# page1.net
KiCad netlist of a schematic drawn in EAGLE
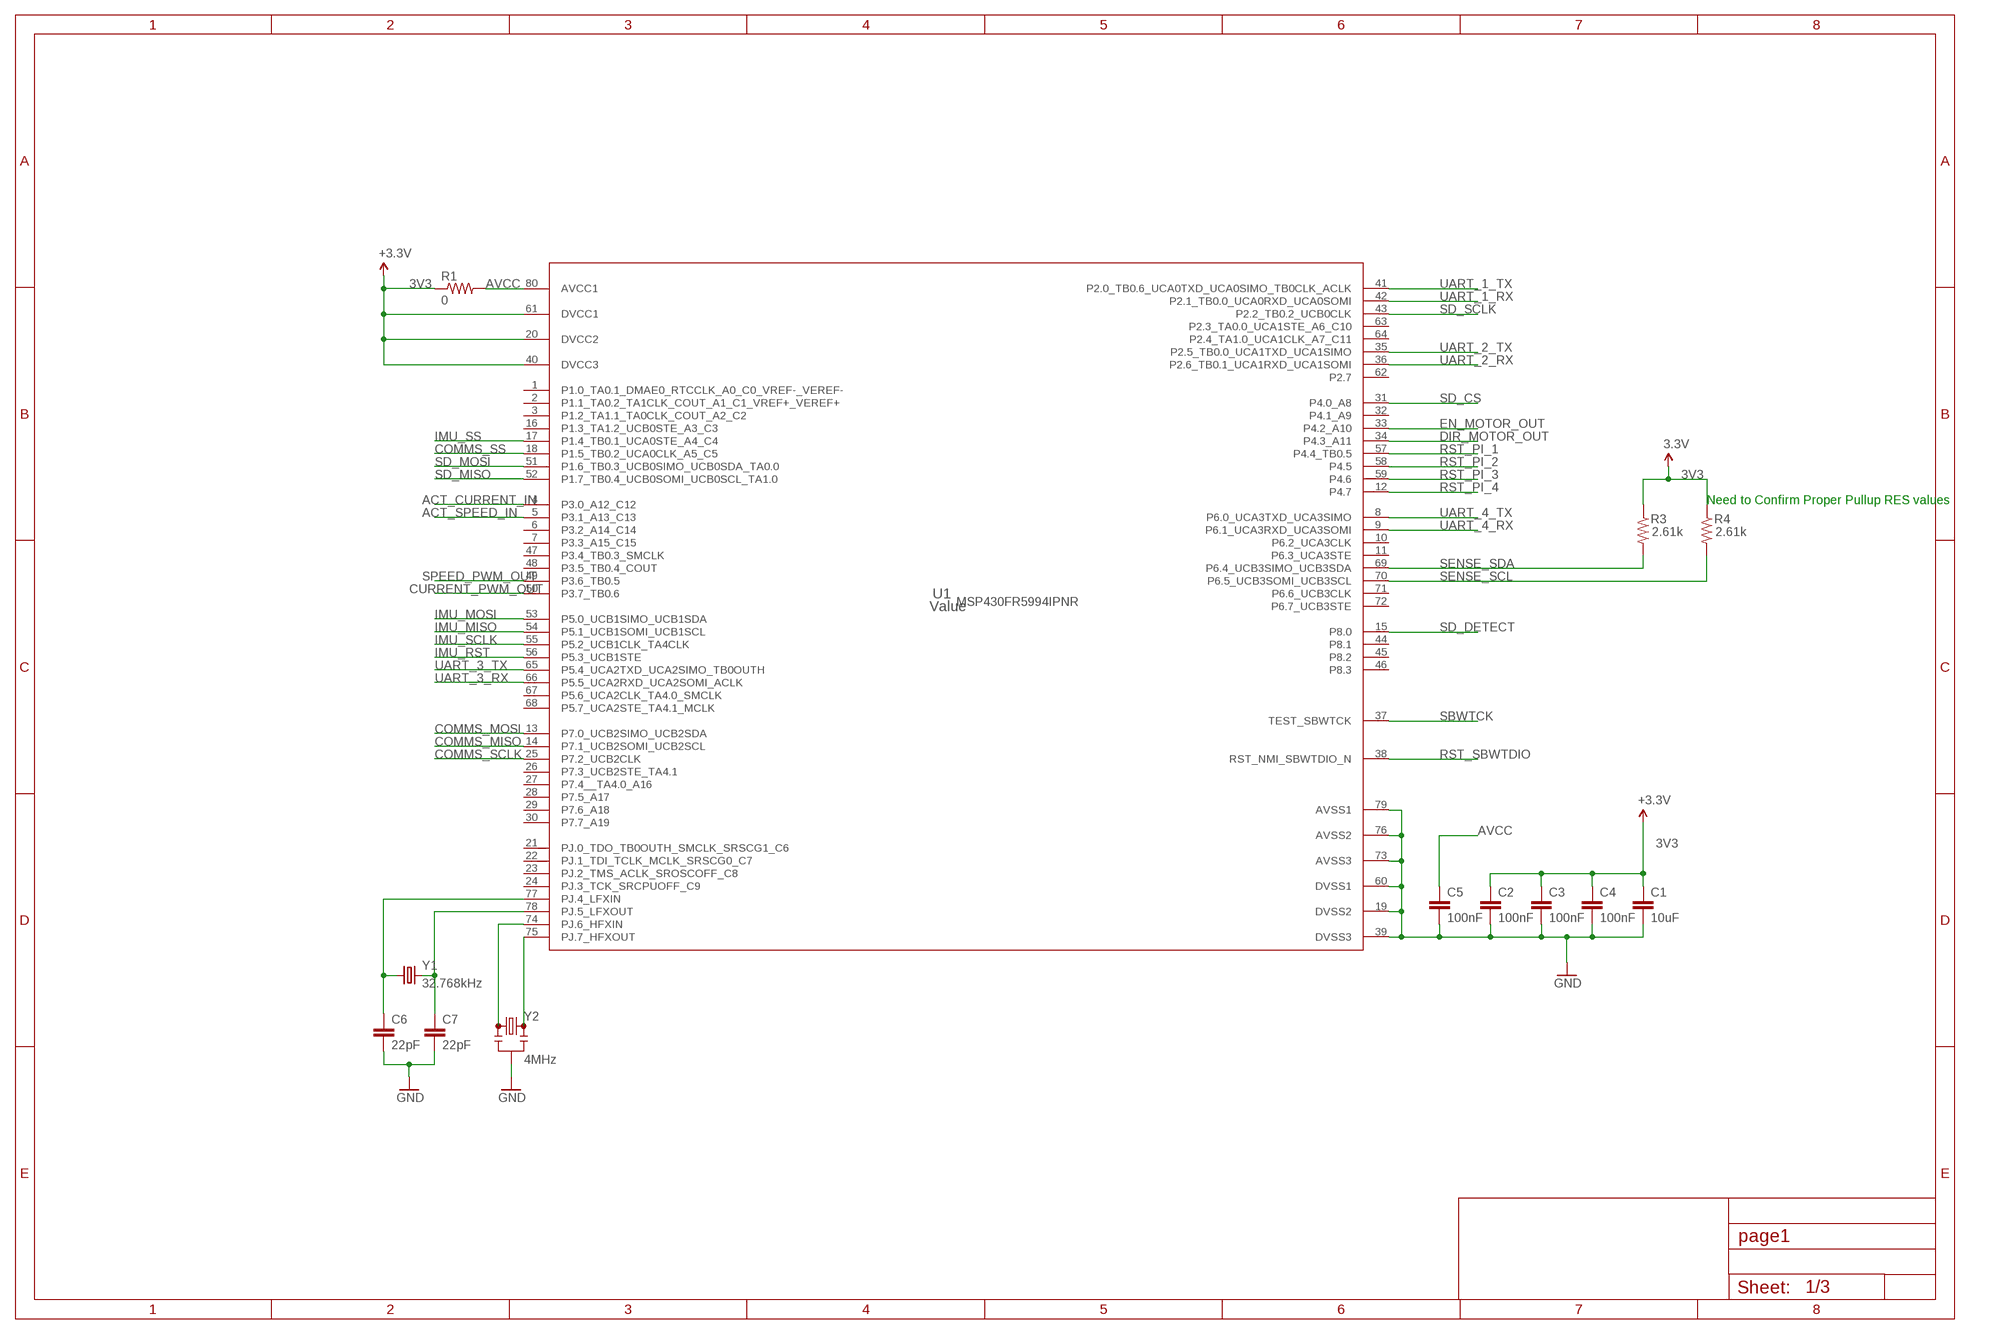
[diagram p0: schematic, sheet 1]
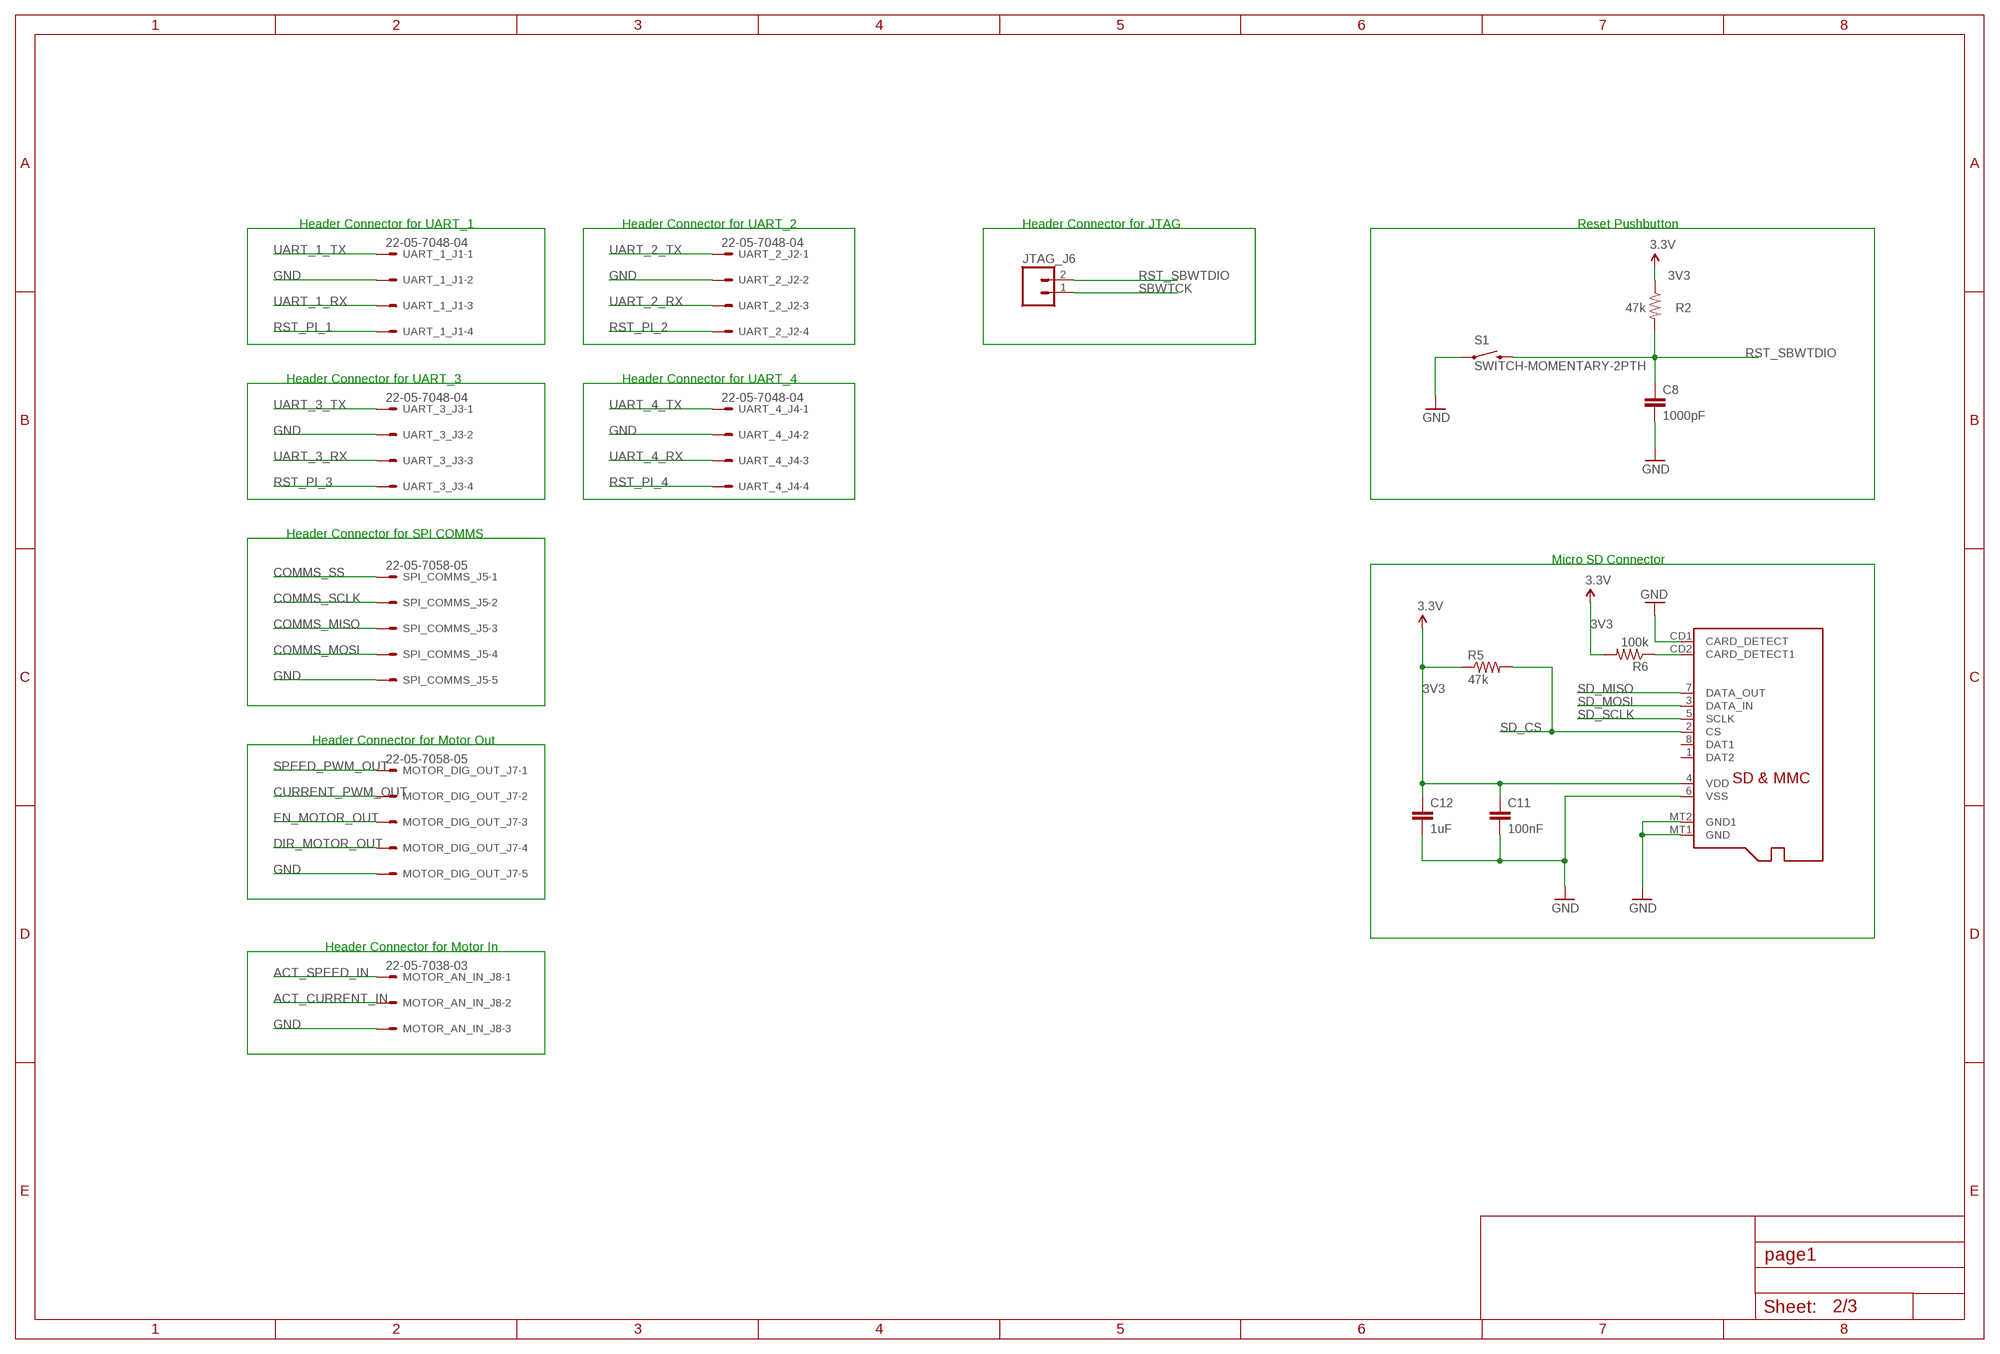
[diagram p1: schematic, sheet 2]
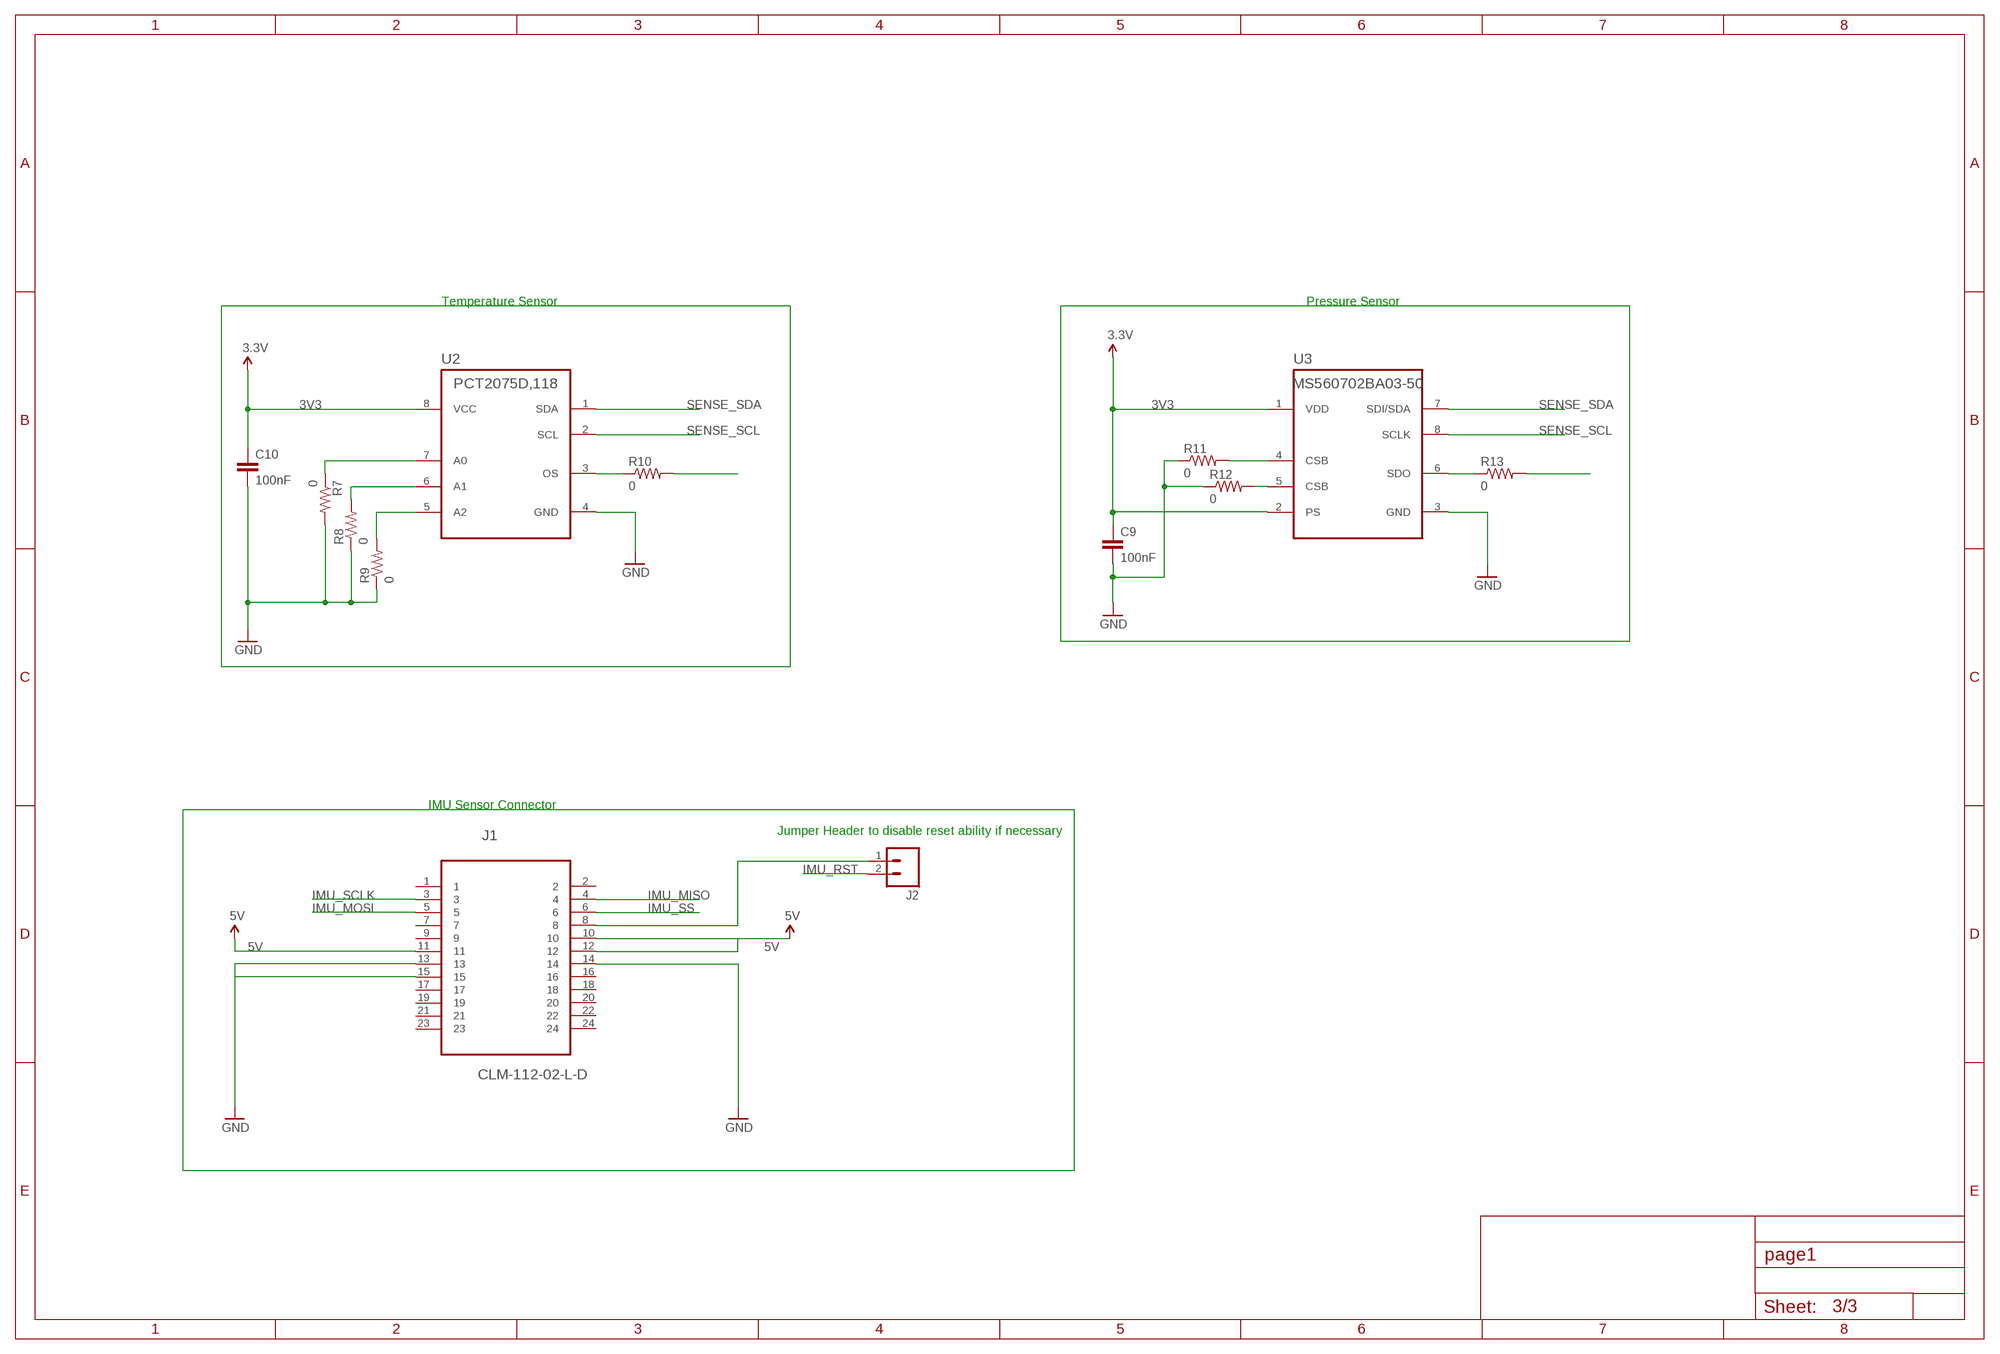
[diagram p2: schematic, sheet 3]

(export (version "E")
  (design (tool "Eeschema 10.0.6"))
  (components
    (comp (ref "C1")
      (value "10uF")
      (footprint "eagle-import:C0603")
      (fields
        (field (name "MANUFACTURER") "Murata")
        (field (name "TOLERANCE") "10%")
        (field (name "VOLTAGE") "10V")
      )
      (libsource (lib "eagle-import") (part "CAP_0603_10UF0"))
    )
    (comp (ref "C2")
      (value "100nF")
      (footprint "eagle-import:C0603")
      (fields
        (field (name "MANUFACTURER") "Murata")
        (field (name "TOLERANCE") "10%")
        (field (name "VOLTAGE") "16V")
      )
      (libsource (lib "eagle-import") (part "CAP_0603_100NF0"))
    )
    (comp (ref "C3")
      (value "100nF")
      (footprint "eagle-import:C0603")
      (fields
        (field (name "MANUFACTURER") "Murata")
        (field (name "TOLERANCE") "10%")
        (field (name "VOLTAGE") "16V")
      )
      (libsource (lib "eagle-import") (part "CAP_0603_100NF0"))
    )
    (comp (ref "C4")
      (value "100nF")
      (footprint "eagle-import:C0603")
      (fields
        (field (name "MANUFACTURER") "Murata")
        (field (name "TOLERANCE") "10%")
        (field (name "VOLTAGE") "16V")
      )
      (libsource (lib "eagle-import") (part "CAP_0603_100NF0"))
    )
    (comp (ref "C5")
      (value "100nF")
      (footprint "eagle-import:C0603")
      (fields
        (field (name "MANUFACTURER") "Murata")
        (field (name "TOLERANCE") "10%")
        (field (name "VOLTAGE") "16V")
      )
      (libsource (lib "eagle-import") (part "CAP_0603_100NF0"))
    )
    (comp (ref "C6")
      (value "22pF")
      (footprint "eagle-import:C0603")
      (fields
        (field (name "MANUFACTURER") "Murata")
        (field (name "TOLERANCE") "5%")
        (field (name "VOLTAGE") "50V")
      )
      (libsource (lib "eagle-import") (part "CAP_0603_22PF0"))
    )
    (comp (ref "C7")
      (value "22pF")
      (footprint "eagle-import:C0603")
      (fields
        (field (name "MANUFACTURER") "Murata")
        (field (name "TOLERANCE") "5%")
        (field (name "VOLTAGE") "50V")
      )
      (libsource (lib "eagle-import") (part "CAP_0603_22PF0"))
    )
    (comp (ref "R1")
      (value "0")
      (footprint "eagle-import:R0603")
      (fields
        (field (name "MANUFACTURER") "Panasonic")
        (field (name "POWER") "1/10W")
        (field (name "TOLERANCE") "JUMPER")
      )
      (libsource (lib "eagle-import") (part "RES_0603_0R0"))
    )
    (comp (ref "R3")
      (value "2.61k")
      (footprint "eagle-import:R0603")
      (fields
        (field (name "MANUFACTURER") "Panasonic")
        (field (name "POWER") "1/10W")
        (field (name "TOLERANCE") "1%")
      )
      (libsource (lib "eagle-import") (part "RES_0603_2R61"))
    )
    (comp (ref "R4")
      (value "2.61k")
      (footprint "eagle-import:R0603")
      (fields
        (field (name "MANUFACTURER") "Panasonic")
        (field (name "POWER") "1/10W")
        (field (name "TOLERANCE") "1%")
      )
      (libsource (lib "eagle-import") (part "RES_0603_2R61"))
    )
    (comp (ref "U1")
      (value "Value")
      (footprint "eagle-import:PN0080A_N")
      (fields
        (field (name "MANUFACTURER") "Texas Instruments")
        (field (name "PARTNUMBER") "MSP430FR5994IPNR")
      )
      (libsource (lib "eagle-import") (part "MSP430FR5994IPNR"))
    )
    (comp (ref "Y1")
      (value "32.768kHz")
      (footprint "eagle-import:CRYSTAL-SMD-3.2X1.5MM")
      (libsource (lib "eagle-import") (part "CRYSTAL3.2X1.5MM"))
    )
    (comp (ref "Y2")
      (value "4MHz")
      (footprint "eagle-import:RESONATOR-SMD_MED")
      (libsource (lib "eagle-import") (part "RESONATOR4MHZ"))
    )
    (comp (ref "C8")
      (value "1000pF")
      (footprint "eagle-import:C0603")
      (fields
        (field (name "MANUFACTURER") "Murata")
        (field (name "TOLERANCE") "10%")
        (field (name "VOLTAGE") "50V")
      )
      (libsource (lib "eagle-import") (part "CAP_0603_1000PF0"))
    )
    (comp (ref "C11")
      (value "100nF")
      (footprint "eagle-import:C0603")
      (fields
        (field (name "MANUFACTURER") "Murata")
        (field (name "TOLERANCE") "10%")
        (field (name "VOLTAGE") "16V")
      )
      (libsource (lib "eagle-import") (part "CAP_0603_100NF0"))
    )
    (comp (ref "C12")
      (value "1uF")
      (footprint "eagle-import:C0603")
      (fields
        (field (name "MANUFACTURER") "Murata")
        (field (name "TOLERANCE") "20%")
        (field (name "VOLTAGE") "10V")
      )
      (libsource (lib "eagle-import") (part "CAP_0603_1UF0"))
    )
    (comp (ref "JTAG_J6")
      (value "M02PTH")
      (footprint "eagle-import:1X02")
      (libsource (lib "eagle-import") (part "M02PTH"))
    )
    (comp (ref "MOTOR_AN_IN_J8")
      (value "22-05-7038-03")
      (footprint "eagle-import:7395-03")
      (libsource (lib "eagle-import") (part "22-?-0305-7038"))
    )
    (comp (ref "MOTOR_DIG_OUT_J7")
      (value "22-05-7058-05")
      (footprint "eagle-import:7395-05")
      (libsource (lib "eagle-import") (part "22-?-0505-7058"))
    )
    (comp (ref "R2")
      (value "47k")
      (footprint "eagle-import:R0603")
      (fields
        (field (name "MANUFACTURER") "Panasonic")
        (field (name "POWER") "1/10W")
        (field (name "TOLERANCE") "1%")
      )
      (libsource (lib "eagle-import") (part "RES_0603_47R0"))
    )
    (comp (ref "R5")
      (value "47k")
      (footprint "eagle-import:R0603")
      (fields
        (field (name "MANUFACTURER") "Panasonic")
        (field (name "POWER") "1/10W")
        (field (name "TOLERANCE") "1%")
      )
      (libsource (lib "eagle-import") (part "RES_0603_47R0"))
    )
    (comp (ref "R6")
      (value "100k")
      (footprint "eagle-import:R0603")
      (fields
        (field (name "MANUFACTURER") "Panasonic")
        (field (name "POWER") "1/10W")
        (field (name "TOLERANCE") "1%")
      )
      (libsource (lib "eagle-import") (part "RES_0603_100R0"))
    )
    (comp (ref "S1")
      (value "SWITCH-MOMENTARY-2PTH")
      (footprint "eagle-import:TACTILE-PTH")
      (libsource (lib "eagle-import") (part "SWITCH-MOMENTARY-2PTH"))
    )
    (comp (ref "SPI_COMMS_J5")
      (value "22-05-7058-05")
      (footprint "eagle-import:7395-05")
      (libsource (lib "eagle-import") (part "22-?-0505-7058"))
    )
    (comp (ref "U$1")
      (value "MICROSD")
      (footprint "eagle-import:MICROSD")
      (libsource (lib "eagle-import") (part "MICROSD"))
    )
    (comp (ref "UART_1_J1")
      (value "22-05-7048-04")
      (footprint "eagle-import:7395-04")
      (libsource (lib "eagle-import") (part "22-?-0405-7048"))
    )
    (comp (ref "UART_2_J2")
      (value "22-05-7048-04")
      (footprint "eagle-import:7395-04")
      (libsource (lib "eagle-import") (part "22-?-0405-7048"))
    )
    (comp (ref "UART_3_J3")
      (value "22-05-7048-04")
      (footprint "eagle-import:7395-04")
      (libsource (lib "eagle-import") (part "22-?-0405-7048"))
    )
    (comp (ref "UART_4_J4")
      (value "22-05-7048-04")
      (footprint "eagle-import:7395-04")
      (libsource (lib "eagle-import") (part "22-?-0405-7048"))
    )
    (comp (ref "C9")
      (value "100nF")
      (footprint "eagle-import:C0603")
      (fields
        (field (name "MANUFACTURER") "Murata")
        (field (name "TOLERANCE") "10%")
        (field (name "VOLTAGE") "16V")
      )
      (libsource (lib "eagle-import") (part "CAP_0603_100NF0"))
    )
    (comp (ref "C10")
      (value "100nF")
      (footprint "eagle-import:C0603")
      (fields
        (field (name "MANUFACTURER") "Murata")
        (field (name "TOLERANCE") "10%")
        (field (name "VOLTAGE") "16V")
      )
      (libsource (lib "eagle-import") (part "CAP_0603_100NF0"))
    )
    (comp (ref "J1")
      (value "CLM-112-02-L-D")
      (footprint "eagle-import:SAMTEC_CLM-112-02-L-D")
      (libsource (lib "eagle-import") (part "CLM-112-02-L-D"))
    )
    (comp (ref "J2")
      (value "M02PTH")
      (footprint "eagle-import:1X02")
      (libsource (lib "eagle-import") (part "M02PTH"))
    )
    (comp (ref "R7")
      (value "0")
      (footprint "eagle-import:R0603")
      (fields
        (field (name "MANUFACTURER") "Panasonic")
        (field (name "POWER") "1/10W")
        (field (name "TOLERANCE") "JUMPER")
      )
      (libsource (lib "eagle-import") (part "RES_0603_0R0"))
    )
    (comp (ref "R8")
      (value "0")
      (footprint "eagle-import:R0603")
      (fields
        (field (name "MANUFACTURER") "Panasonic")
        (field (name "POWER") "1/10W")
        (field (name "TOLERANCE") "JUMPER")
      )
      (libsource (lib "eagle-import") (part "RES_0603_0R0"))
    )
    (comp (ref "R9")
      (value "0")
      (footprint "eagle-import:R0603")
      (fields
        (field (name "MANUFACTURER") "Panasonic")
        (field (name "POWER") "1/10W")
        (field (name "TOLERANCE") "JUMPER")
      )
      (libsource (lib "eagle-import") (part "RES_0603_0R0"))
    )
    (comp (ref "R10")
      (value "0")
      (footprint "eagle-import:R0603")
      (fields
        (field (name "MANUFACTURER") "Panasonic")
        (field (name "POWER") "1/10W")
        (field (name "TOLERANCE") "JUMPER")
      )
      (libsource (lib "eagle-import") (part "RES_0603_0R0"))
    )
    (comp (ref "R11")
      (value "0")
      (footprint "eagle-import:R0603")
      (fields
        (field (name "MANUFACTURER") "Panasonic")
        (field (name "POWER") "1/10W")
        (field (name "TOLERANCE") "JUMPER")
      )
      (libsource (lib "eagle-import") (part "RES_0603_0R0"))
    )
    (comp (ref "R12")
      (value "0")
      (footprint "eagle-import:R0603")
      (fields
        (field (name "MANUFACTURER") "Panasonic")
        (field (name "POWER") "1/10W")
        (field (name "TOLERANCE") "JUMPER")
      )
      (libsource (lib "eagle-import") (part "RES_0603_0R0"))
    )
    (comp (ref "R13")
      (value "0")
      (footprint "eagle-import:R0603")
      (fields
        (field (name "MANUFACTURER") "Panasonic")
        (field (name "POWER") "1/10W")
        (field (name "TOLERANCE") "JUMPER")
      )
      (libsource (lib "eagle-import") (part "RES_0603_0R0"))
    )
    (comp (ref "U2")
      (value "PCT2075D,118")
      (footprint "eagle-import:SOIC127P130X0600-8N")
      (fields (field (name "MANUFACTURER") "NXP"))
      (libsource (lib "eagle-import") (part "PCT2075SOIC8D,118"))
    )
    (comp (ref "U3")
      (value "MS560702BA03-50")
      (footprint "eagle-import:SMD125P110X060-8N")
      (fields (field (name "MANUFACTURER") "TE Connectivity"))
      (libsource (lib "eagle-import") (part "MS5607_8SMD-02BA03"))
    )
  )
  (nets
    (net (code "1") (name "3V3") (class "Default")
      (node (ref "C1") (pin "1") (pinfunction "1_1") (pintype "passive"))
      (node (ref "C10") (pin "1") (pinfunction "1_1") (pintype "passive"))
      (node (ref "C11") (pin "1") (pinfunction "1_1") (pintype "passive"))
      (node (ref "C12") (pin "1") (pinfunction "1_1") (pintype "passive"))
      (node (ref "C2") (pin "1") (pinfunction "1_1") (pintype "passive"))
      (node (ref "C3") (pin "1") (pinfunction "1_1") (pintype "passive"))
      (node (ref "C4") (pin "1") (pinfunction "1_1") (pintype "passive"))
      (node (ref "C9") (pin "1") (pinfunction "1_1") (pintype "passive"))
      (node (ref "R1") (pin "1") (pinfunction "1_1") (pintype "passive"))
      (node (ref "R2") (pin "1") (pinfunction "1_1") (pintype "passive"))
      (node (ref "R3") (pin "1") (pinfunction "1_1") (pintype "passive"))
      (node (ref "R4") (pin "1") (pinfunction "1_1") (pintype "passive"))
      (node (ref "R5") (pin "1") (pinfunction "1_1") (pintype "passive"))
      (node (ref "R6") (pin "2") (pinfunction "2_2") (pintype "passive"))
      (node (ref "U$1") (pin "4") (pinfunction "VDD_4") (pintype "power_in"))
      (node (ref "U1") (pin "20") (pinfunction "DVCC2_20") (pintype "power_in"))
      (node (ref "U1") (pin "40") (pinfunction "DVCC3_40") (pintype "power_in"))
      (node (ref "U1") (pin "61") (pinfunction "DVCC1_61") (pintype "power_in"))
      (node (ref "U2") (pin "8") (pinfunction "VCC_8") (pintype "power_in"))
      (node (ref "U3") (pin "1") (pinfunction "VDD_1") (pintype "power_in"))
      (node (ref "U3") (pin "2") (pinfunction "PS_2") (pintype "input"))
    )
    (net (code "2") (name "5V") (class "Default")
      (node (ref "J1") (pin "10") (pinfunction "10_10") (pintype "passive"))
      (node (ref "J1") (pin "11") (pinfunction "11_11") (pintype "passive"))
      (node (ref "J1") (pin "12") (pinfunction "12_12") (pintype "passive"))
    )
    (net (code "3") (name "ACT_CURRENT_IN") (class "Default")
      (node (ref "MOTOR_AN_IN_J8") (pin "2") (pinfunction "S_2") (pintype "passive"))
      (node (ref "U1") (pin "4") (pinfunction "P3.0_A12_C12_4") (pintype "bidirectional"))
    )
    (net (code "4") (name "ACT_SPEED_IN") (class "Default")
      (node (ref "MOTOR_AN_IN_J8") (pin "1") (pinfunction "S_1") (pintype "passive"))
      (node (ref "U1") (pin "5") (pinfunction "P3.1_A13_C13_5") (pintype "bidirectional"))
    )
    (net (code "5") (name "AVCC") (class "Default")
      (node (ref "C5") (pin "1") (pinfunction "1_1") (pintype "passive"))
      (node (ref "R1") (pin "2") (pinfunction "2_2") (pintype "passive"))
      (node (ref "U1") (pin "80") (pinfunction "AVCC1_80") (pintype "power_in"))
    )
    (net (code "6") (name "COMMS_MISO") (class "Default")
      (node (ref "SPI_COMMS_J5") (pin "3") (pinfunction "S_3") (pintype "passive"))
      (node (ref "U1") (pin "14") (pinfunction "P7.1_UCB2SOMI_UCB2SCL_14") (pintype "bidirectional"))
    )
    (net (code "7") (name "COMMS_MOSI") (class "Default")
      (node (ref "SPI_COMMS_J5") (pin "4") (pinfunction "S_4") (pintype "passive"))
      (node (ref "U1") (pin "13") (pinfunction "P7.0_UCB2SIMO_UCB2SDA_13") (pintype "bidirectional"))
    )
    (net (code "8") (name "COMMS_SCLK") (class "Default")
      (node (ref "SPI_COMMS_J5") (pin "2") (pinfunction "S_2") (pintype "passive"))
      (node (ref "U1") (pin "25") (pinfunction "P7.2_UCB2CLK_25") (pintype "bidirectional"))
    )
    (net (code "9") (name "COMMS_SS") (class "Default")
      (node (ref "SPI_COMMS_J5") (pin "1") (pinfunction "S_1") (pintype "passive"))
      (node (ref "U1") (pin "18") (pinfunction "P1.5_TB0.2_UCA0CLK_A5_C5_18") (pintype "bidirectional"))
    )
    (net (code "10") (name "CURRENT_PWM_OUT") (class "Default")
      (node (ref "MOTOR_DIG_OUT_J7") (pin "2") (pinfunction "S_2") (pintype "passive"))
      (node (ref "U1") (pin "50") (pinfunction "P3.7_TB0.6_50") (pintype "bidirectional"))
    )
    (net (code "11") (name "DIR_MOTOR_OUT") (class "Default")
      (node (ref "MOTOR_DIG_OUT_J7") (pin "4") (pinfunction "S_4") (pintype "passive"))
      (node (ref "U1") (pin "34") (pinfunction "P4.3_A11_34") (pintype "bidirectional"))
    )
    (net (code "12") (name "EN_MOTOR_OUT") (class "Default")
      (node (ref "MOTOR_DIG_OUT_J7") (pin "3") (pinfunction "S_3") (pintype "passive"))
      (node (ref "U1") (pin "33") (pinfunction "P4.2_A10_33") (pintype "bidirectional"))
    )
    (net (code "13") (name "GND") (class "Default")
      (node (ref "C1") (pin "2") (pinfunction "2_2") (pintype "passive"))
      (node (ref "C10") (pin "2") (pinfunction "2_2") (pintype "passive"))
      (node (ref "C11") (pin "2") (pinfunction "2_2") (pintype "passive"))
      (node (ref "C12") (pin "2") (pinfunction "2_2") (pintype "passive"))
      (node (ref "C2") (pin "2") (pinfunction "2_2") (pintype "passive"))
      (node (ref "C3") (pin "2") (pinfunction "2_2") (pintype "passive"))
      (node (ref "C4") (pin "2") (pinfunction "2_2") (pintype "passive"))
      (node (ref "C5") (pin "2") (pinfunction "2_2") (pintype "passive"))
      (node (ref "C6") (pin "2") (pinfunction "2_2") (pintype "passive"))
      (node (ref "C7") (pin "2") (pinfunction "2_2") (pintype "passive"))
      (node (ref "C8") (pin "2") (pinfunction "2_2") (pintype "passive"))
      (node (ref "C9") (pin "2") (pinfunction "2_2") (pintype "passive"))
      (node (ref "J1") (pin "13") (pinfunction "13_13") (pintype "passive"))
      (node (ref "J1") (pin "14") (pinfunction "14_14") (pintype "passive"))
      (node (ref "J1") (pin "15") (pinfunction "15_15") (pintype "passive"))
      (node (ref "MOTOR_AN_IN_J8") (pin "3") (pinfunction "S_3") (pintype "passive"))
      (node (ref "MOTOR_DIG_OUT_J7") (pin "5") (pinfunction "S_5") (pintype "passive"))
      (node (ref "R11") (pin "1") (pinfunction "1_1") (pintype "passive"))
      (node (ref "R12") (pin "1") (pinfunction "1_1") (pintype "passive"))
      (node (ref "R7") (pin "2") (pinfunction "2_2") (pintype "passive"))
      (node (ref "R8") (pin "1") (pinfunction "1_1") (pintype "passive"))
      (node (ref "R9") (pin "1") (pinfunction "1_1") (pintype "passive"))
      (node (ref "S1") (pin "1") (pinfunction "1_1") (pintype "passive"))
      (node (ref "SPI_COMMS_J5") (pin "5") (pinfunction "S_5") (pintype "passive"))
      (node (ref "U$1") (pin "6") (pinfunction "VSS_6") (pintype "power_in"))
      (node (ref "U$1") (pin "CD1") (pinfunction "CARD_DETECT_CD1") (pintype "passive"))
      (node (ref "U$1") (pin "MT1") (pinfunction "GND_MT1") (pintype "power_in"))
      (node (ref "U$1") (pin "MT2") (pinfunction "GND1_MT2") (pintype "power_in"))
      (node (ref "U1") (pin "19") (pinfunction "DVSS2_19") (pintype "power_in"))
      (node (ref "U1") (pin "39") (pinfunction "DVSS3_39") (pintype "power_in"))
      (node (ref "U1") (pin "60") (pinfunction "DVSS1_60") (pintype "power_in"))
      (node (ref "U1") (pin "73") (pinfunction "AVSS3_73") (pintype "power_in"))
      (node (ref "U1") (pin "76") (pinfunction "AVSS2_76") (pintype "power_in"))
      (node (ref "U1") (pin "79") (pinfunction "AVSS1_79") (pintype "power_in"))
      (node (ref "U2") (pin "4") (pinfunction "GND_4") (pintype "power_in"))
      (node (ref "U3") (pin "3") (pinfunction "GND_3") (pintype "power_in"))
      (node (ref "UART_1_J1") (pin "2") (pinfunction "S_2") (pintype "passive"))
      (node (ref "UART_2_J2") (pin "2") (pinfunction "S_2") (pintype "passive"))
      (node (ref "UART_3_J3") (pin "2") (pinfunction "S_2") (pintype "passive"))
      (node (ref "UART_4_J4") (pin "2") (pinfunction "S_2") (pintype "passive"))
      (node (ref "Y2") (pin "2") (pinfunction "2_2") (pintype "passive"))
    )
    (net (code "14") (name "IMU_MISO") (class "Default")
      (node (ref "J1") (pin "4") (pinfunction "4_4") (pintype "passive"))
      (node (ref "U1") (pin "54") (pinfunction "P5.1_UCB1SOMI_UCB1SCL_54") (pintype "bidirectional"))
    )
    (net (code "15") (name "IMU_MOSI") (class "Default")
      (node (ref "J1") (pin "5") (pinfunction "5_5") (pintype "passive"))
      (node (ref "U1") (pin "53") (pinfunction "P5.0_UCB1SIMO_UCB1SDA_53") (pintype "bidirectional"))
    )
    (net (code "16") (name "IMU_RST") (class "Default")
      (node (ref "J2") (pin "2") (pinfunction "2_2") (pintype "passive"))
      (node (ref "U1") (pin "56") (pinfunction "P5.3_UCB1STE_56") (pintype "bidirectional"))
    )
    (net (code "17") (name "IMU_SCLK") (class "Default")
      (node (ref "J1") (pin "3") (pinfunction "3_3") (pintype "passive"))
      (node (ref "U1") (pin "55") (pinfunction "P5.2_UCB1CLK_TA4CLK_55") (pintype "bidirectional"))
    )
    (net (code "18") (name "IMU_SS") (class "Default")
      (node (ref "J1") (pin "6") (pinfunction "6_6") (pintype "passive"))
      (node (ref "U1") (pin "17") (pinfunction "P1.4_TB0.1_UCA0STE_A4_C4_17") (pintype "bidirectional"))
    )
    (net (code "19") (name "Net-(J1-Pad8)") (class "Default")
      (node (ref "J1") (pin "8") (pinfunction "8_8") (pintype "passive"))
      (node (ref "J2") (pin "1") (pinfunction "1_1") (pintype "passive"))
    )
    (net (code "20") (name "Net-(R11-Pad2)") (class "Default")
      (node (ref "R11") (pin "2") (pinfunction "2_2") (pintype "passive"))
      (node (ref "U3") (pin "4") (pinfunction "CSB_4") (pintype "input"))
    )
    (net (code "21") (name "Net-(R12-Pad2)") (class "Default")
      (node (ref "R12") (pin "2") (pinfunction "2_2") (pintype "passive"))
      (node (ref "U3") (pin "5") (pinfunction "CSB_5") (pintype "output"))
    )
    (net (code "22") (name "Net-(U$1-CARD_DETECT1)") (class "Default")
      (node (ref "R6") (pin "1") (pinfunction "1_1") (pintype "passive"))
      (node (ref "U$1") (pin "CD2") (pinfunction "CARD_DETECT1_CD2") (pintype "passive"))
    )
    (net (code "23") (name "Net-(U1-PJ.4_LFXIN)") (class "Default")
      (node (ref "C6") (pin "1") (pinfunction "1_1") (pintype "passive"))
      (node (ref "U1") (pin "77") (pinfunction "PJ.4_LFXIN_77") (pintype "bidirectional"))
      (node (ref "Y1") (pin "P$1") (pinfunction "1_P$1") (pintype "passive"))
    )
    (net (code "24") (name "Net-(U1-PJ.5_LFXOUT)") (class "Default")
      (node (ref "C7") (pin "1") (pinfunction "1_1") (pintype "passive"))
      (node (ref "U1") (pin "78") (pinfunction "PJ.5_LFXOUT_78") (pintype "bidirectional"))
      (node (ref "Y1") (pin "P$2") (pinfunction "2_P$2") (pintype "passive"))
    )
    (net (code "25") (name "Net-(U1-PJ.6_HFXIN)") (class "Default")
      (node (ref "U1") (pin "74") (pinfunction "PJ.6_HFXIN_74") (pintype "bidirectional"))
      (node (ref "Y2") (pin "1") (pinfunction "1_1") (pintype "passive"))
    )
    (net (code "26") (name "Net-(U1-PJ.7_HFXOUT)") (class "Default")
      (node (ref "U1") (pin "75") (pinfunction "PJ.7_HFXOUT_75") (pintype "bidirectional"))
      (node (ref "Y2") (pin "3") (pinfunction "3_3") (pintype "passive"))
    )
    (net (code "27") (name "Net-(U2-A0)") (class "Default")
      (node (ref "R7") (pin "1") (pinfunction "1_1") (pintype "passive"))
      (node (ref "U2") (pin "7") (pinfunction "A0_7") (pintype "input"))
    )
    (net (code "28") (name "Net-(U2-A1)") (class "Default")
      (node (ref "R8") (pin "2") (pinfunction "2_2") (pintype "passive"))
      (node (ref "U2") (pin "6") (pinfunction "A1_6") (pintype "input"))
    )
    (net (code "29") (name "Net-(U2-A2)") (class "Default")
      (node (ref "R9") (pin "2") (pinfunction "2_2") (pintype "passive"))
      (node (ref "U2") (pin "5") (pinfunction "A2_5") (pintype "input"))
    )
    (net (code "30") (name "Net-(U2-OS)") (class "Default")
      (node (ref "R10") (pin "1") (pinfunction "1_1") (pintype "passive"))
      (node (ref "U2") (pin "3") (pinfunction "OS_3") (pintype "output"))
    )
    (net (code "31") (name "Net-(U3-SDO)") (class "Default")
      (node (ref "R13") (pin "1") (pinfunction "1_1") (pintype "passive"))
      (node (ref "U3") (pin "6") (pinfunction "SDO_6") (pintype "output"))
    )
    (net (code "32") (name "RST_PI_1") (class "Default")
      (node (ref "U1") (pin "57") (pinfunction "P4.4_TB0.5_57") (pintype "bidirectional"))
      (node (ref "UART_1_J1") (pin "4") (pinfunction "S_4") (pintype "passive"))
    )
    (net (code "33") (name "RST_PI_2") (class "Default")
      (node (ref "U1") (pin "58") (pinfunction "P4.5_58") (pintype "bidirectional"))
      (node (ref "UART_2_J2") (pin "4") (pinfunction "S_4") (pintype "passive"))
    )
    (net (code "34") (name "RST_PI_3") (class "Default")
      (node (ref "U1") (pin "59") (pinfunction "P4.6_59") (pintype "bidirectional"))
      (node (ref "UART_3_J3") (pin "4") (pinfunction "S_4") (pintype "passive"))
    )
    (net (code "35") (name "RST_PI_4") (class "Default")
      (node (ref "U1") (pin "12") (pinfunction "P4.7_12") (pintype "bidirectional"))
      (node (ref "UART_4_J4") (pin "4") (pinfunction "S_4") (pintype "passive"))
    )
    (net (code "36") (name "RST_SBWTDIO") (class "Default")
      (node (ref "C8") (pin "1") (pinfunction "1_1") (pintype "passive"))
      (node (ref "JTAG_J6") (pin "2") (pinfunction "2_2") (pintype "passive"))
      (node (ref "R2") (pin "2") (pinfunction "2_2") (pintype "passive"))
      (node (ref "S1") (pin "3") (pinfunction "2_3") (pintype "passive"))
      (node (ref "U1") (pin "38") (pinfunction "RST_NMI_SBWTDIO_N_38") (pintype "bidirectional"))
    )
    (net (code "37") (name "SBWTCK") (class "Default")
      (node (ref "JTAG_J6") (pin "1") (pinfunction "1_1") (pintype "passive"))
      (node (ref "U1") (pin "37") (pinfunction "TEST_SBWTCK_37") (pintype "input"))
    )
    (net (code "38") (name "SD_CS") (class "Default")
      (node (ref "R5") (pin "2") (pinfunction "2_2") (pintype "passive"))
      (node (ref "U$1") (pin "2") (pinfunction "CS_2") (pintype "input"))
      (node (ref "U1") (pin "31") (pinfunction "P4.0_A8_31") (pintype "bidirectional"))
    )
    (net (code "39") (name "SD_DETECT") (class "Default")
      (node (ref "U1") (pin "15") (pinfunction "P8.0_15") (pintype "bidirectional"))
    )
    (net (code "40") (name "SD_MISO") (class "Default")
      (node (ref "U$1") (pin "7") (pinfunction "DATA_OUT_7") (pintype "output"))
      (node (ref "U1") (pin "52") (pinfunction "P1.7_TB0.4_UCB0SOMI_UCB0SCL_TA1.0_52") (pintype "bidirectional"))
    )
    (net (code "41") (name "SD_MOSI") (class "Default")
      (node (ref "U$1") (pin "3") (pinfunction "DATA_IN_3") (pintype "input"))
      (node (ref "U1") (pin "51") (pinfunction "P1.6_TB0.3_UCB0SIMO_UCB0SDA_TA0.0_51") (pintype "bidirectional"))
    )
    (net (code "42") (name "SD_SCLK") (class "Default")
      (node (ref "U$1") (pin "5") (pinfunction "SCLK_5") (pintype "input"))
      (node (ref "U1") (pin "43") (pinfunction "P2.2_TB0.2_UCB0CLK_43") (pintype "bidirectional"))
    )
    (net (code "43") (name "SENSE_SCL") (class "Default")
      (node (ref "R4") (pin "2") (pinfunction "2_2") (pintype "passive"))
      (node (ref "U1") (pin "70") (pinfunction "P6.5_UCB3SOMI_UCB3SCL_70") (pintype "bidirectional"))
      (node (ref "U2") (pin "2") (pinfunction "SCL_2") (pintype "input"))
      (node (ref "U3") (pin "8") (pinfunction "SCLK_8") (pintype "input"))
    )
    (net (code "44") (name "SENSE_SDA") (class "Default")
      (node (ref "R3") (pin "2") (pinfunction "2_2") (pintype "passive"))
      (node (ref "U1") (pin "69") (pinfunction "P6.4_UCB3SIMO_UCB3SDA_69") (pintype "bidirectional"))
      (node (ref "U2") (pin "1") (pinfunction "SDA_1") (pintype "bidirectional"))
      (node (ref "U3") (pin "7") (pinfunction "SDI/SDA_7") (pintype "bidirectional"))
    )
    (net (code "45") (name "SPEED_PWM_OUT") (class "Default")
      (node (ref "MOTOR_DIG_OUT_J7") (pin "1") (pinfunction "S_1") (pintype "passive"))
      (node (ref "U1") (pin "49") (pinfunction "P3.6_TB0.5_49") (pintype "bidirectional"))
    )
    (net (code "46") (name "UART_1_RX") (class "Default")
      (node (ref "U1") (pin "42") (pinfunction "P2.1_TB0.0_UCA0RXD_UCA0SOMI_42") (pintype "bidirectional"))
      (node (ref "UART_1_J1") (pin "3") (pinfunction "S_3") (pintype "passive"))
    )
    (net (code "47") (name "UART_1_TX") (class "Default")
      (node (ref "U1") (pin "41") (pinfunction "P2.0_TB0.6_UCA0TXD_UCA0SIMO_TB0CLK_ACLK_41") (pintype "bidirectional"))
      (node (ref "UART_1_J1") (pin "1") (pinfunction "S_1") (pintype "passive"))
    )
    (net (code "48") (name "UART_2_RX") (class "Default")
      (node (ref "U1") (pin "36") (pinfunction "P2.6_TB0.1_UCA1RXD_UCA1SOMI_36") (pintype "bidirectional"))
      (node (ref "UART_2_J2") (pin "3") (pinfunction "S_3") (pintype "passive"))
    )
    (net (code "49") (name "UART_2_TX") (class "Default")
      (node (ref "U1") (pin "35") (pinfunction "P2.5_TB0.0_UCA1TXD_UCA1SIMO_35") (pintype "bidirectional"))
      (node (ref "UART_2_J2") (pin "1") (pinfunction "S_1") (pintype "passive"))
    )
    (net (code "50") (name "UART_3_RX") (class "Default")
      (node (ref "U1") (pin "66") (pinfunction "P5.5_UCA2RXD_UCA2SOMI_ACLK_66") (pintype "bidirectional"))
      (node (ref "UART_3_J3") (pin "3") (pinfunction "S_3") (pintype "passive"))
    )
    (net (code "51") (name "UART_3_TX") (class "Default")
      (node (ref "U1") (pin "65") (pinfunction "P5.4_UCA2TXD_UCA2SIMO_TB0OUTH_65") (pintype "bidirectional"))
      (node (ref "UART_3_J3") (pin "1") (pinfunction "S_1") (pintype "passive"))
    )
    (net (code "52") (name "UART_4_RX") (class "Default")
      (node (ref "U1") (pin "9") (pinfunction "P6.1_UCA3RXD_UCA3SOMI_9") (pintype "bidirectional"))
      (node (ref "UART_4_J4") (pin "3") (pinfunction "S_3") (pintype "passive"))
    )
    (net (code "53") (name "UART_4_TX") (class "Default")
      (node (ref "U1") (pin "8") (pinfunction "P6.0_UCA3TXD_UCA3SIMO_8") (pintype "bidirectional"))
      (node (ref "UART_4_J4") (pin "1") (pinfunction "S_1") (pintype "passive"))
    )
    (net (code "54") (name "unconnected-(J1-Pad1)") (class "Default")
      (node (ref "J1") (pin "1") (pinfunction "1_1") (pintype "passive"))
    )
    (net (code "55") (name "unconnected-(J1-Pad2)") (class "Default")
      (node (ref "J1") (pin "2") (pinfunction "2_2") (pintype "passive"))
    )
    (net (code "56") (name "unconnected-(J1-Pad7)") (class "Default")
      (node (ref "J1") (pin "7") (pinfunction "7_7") (pintype "passive"))
    )
    (net (code "57") (name "unconnected-(J1-Pad9)") (class "Default")
      (node (ref "J1") (pin "9") (pinfunction "9_9") (pintype "passive"))
    )
    (net (code "58") (name "unconnected-(J1-Pad16)") (class "Default")
      (node (ref "J1") (pin "16") (pinfunction "16_16") (pintype "passive"))
    )
    (net (code "59") (name "unconnected-(J1-Pad17)") (class "Default")
      (node (ref "J1") (pin "17") (pinfunction "17_17") (pintype "passive"))
    )
    (net (code "60") (name "unconnected-(J1-Pad18)") (class "Default")
      (node (ref "J1") (pin "18") (pinfunction "18_18") (pintype "passive"))
    )
    (net (code "61") (name "unconnected-(J1-Pad19)") (class "Default")
      (node (ref "J1") (pin "19") (pinfunction "19_19") (pintype "passive"))
    )
    (net (code "62") (name "unconnected-(J1-Pad20)") (class "Default")
      (node (ref "J1") (pin "20") (pinfunction "20_20") (pintype "passive"))
    )
    (net (code "63") (name "unconnected-(J1-Pad21)") (class "Default")
      (node (ref "J1") (pin "21") (pinfunction "21_21") (pintype "passive"))
    )
    (net (code "64") (name "unconnected-(J1-Pad22)") (class "Default")
      (node (ref "J1") (pin "22") (pinfunction "22_22") (pintype "passive"))
    )
    (net (code "65") (name "unconnected-(J1-Pad23)") (class "Default")
      (node (ref "J1") (pin "23") (pinfunction "23_23") (pintype "passive"))
    )
    (net (code "66") (name "unconnected-(J1-Pad24)") (class "Default")
      (node (ref "J1") (pin "24") (pinfunction "24_24") (pintype "passive"))
    )
    (net (code "67") (name "unconnected-(R10-Pad2)") (class "Default")
      (node (ref "R10") (pin "2") (pinfunction "2_2") (pintype "passive"))
    )
    (net (code "68") (name "unconnected-(R13-Pad2)") (class "Default")
      (node (ref "R13") (pin "2") (pinfunction "2_2") (pintype "passive"))
    )
    (net (code "69") (name "unconnected-(U$1-DAT1-Pad8)") (class "Default")
      (node (ref "U$1") (pin "8") (pinfunction "DAT1_8") (pintype "bidirectional"))
    )
    (net (code "70") (name "unconnected-(U$1-DAT2-Pad1)") (class "Default")
      (node (ref "U$1") (pin "1") (pinfunction "DAT2_1") (pintype "bidirectional"))
    )
    (net (code "71") (name "unconnected-(U1-P1.0_TA0.1_DMAE0_RTCCLK_A0_C0_VREF-_VEREF--Pad1)") (class "Default")
      (node (ref "U1") (pin "1") (pinfunction "P1.0_TA0.1_DMAE0_RTCCLK_A0_C0_VREF-_VEREF-_1") (pintype "bidirectional"))
    )
    (net (code "72") (name "unconnected-(U1-P1.1_TA0.2_TA1CLK_COUT_A1_C1_VREF+_VEREF+-Pad2)") (class "Default")
      (node (ref "U1") (pin "2") (pinfunction "P1.1_TA0.2_TA1CLK_COUT_A1_C1_VREF+_VEREF+_2") (pintype "bidirectional"))
    )
    (net (code "73") (name "unconnected-(U1-P1.2_TA1.1_TA0CLK_COUT_A2_C2-Pad3)") (class "Default")
      (node (ref "U1") (pin "3") (pinfunction "P1.2_TA1.1_TA0CLK_COUT_A2_C2_3") (pintype "bidirectional"))
    )
    (net (code "74") (name "unconnected-(U1-P1.3_TA1.2_UCB0STE_A3_C3-Pad16)") (class "Default")
      (node (ref "U1") (pin "16") (pinfunction "P1.3_TA1.2_UCB0STE_A3_C3_16") (pintype "bidirectional"))
    )
    (net (code "75") (name "unconnected-(U1-P2.3_TA0.0_UCA1STE_A6_C10-Pad63)") (class "Default")
      (node (ref "U1") (pin "63") (pinfunction "P2.3_TA0.0_UCA1STE_A6_C10_63") (pintype "bidirectional"))
    )
    (net (code "76") (name "unconnected-(U1-P2.4_TA1.0_UCA1CLK_A7_C11-Pad64)") (class "Default")
      (node (ref "U1") (pin "64") (pinfunction "P2.4_TA1.0_UCA1CLK_A7_C11_64") (pintype "bidirectional"))
    )
    (net (code "77") (name "unconnected-(U1-P2.7-Pad62)") (class "Default")
      (node (ref "U1") (pin "62") (pinfunction "P2.7_62") (pintype "bidirectional"))
    )
    (net (code "78") (name "unconnected-(U1-P3.2_A14_C14-Pad6)") (class "Default")
      (node (ref "U1") (pin "6") (pinfunction "P3.2_A14_C14_6") (pintype "bidirectional"))
    )
    (net (code "79") (name "unconnected-(U1-P3.3_A15_C15-Pad7)") (class "Default")
      (node (ref "U1") (pin "7") (pinfunction "P3.3_A15_C15_7") (pintype "bidirectional"))
    )
    (net (code "80") (name "unconnected-(U1-P3.4_TB0.3_SMCLK-Pad47)") (class "Default")
      (node (ref "U1") (pin "47") (pinfunction "P3.4_TB0.3_SMCLK_47") (pintype "bidirectional"))
    )
    (net (code "81") (name "unconnected-(U1-P3.5_TB0.4_COUT-Pad48)") (class "Default")
      (node (ref "U1") (pin "48") (pinfunction "P3.5_TB0.4_COUT_48") (pintype "bidirectional"))
    )
    (net (code "82") (name "unconnected-(U1-P4.1_A9-Pad32)") (class "Default")
      (node (ref "U1") (pin "32") (pinfunction "P4.1_A9_32") (pintype "bidirectional"))
    )
    (net (code "83") (name "unconnected-(U1-P5.6_UCA2CLK_TA4.0_SMCLK-Pad67)") (class "Default")
      (node (ref "U1") (pin "67") (pinfunction "P5.6_UCA2CLK_TA4.0_SMCLK_67") (pintype "bidirectional"))
    )
    (net (code "84") (name "unconnected-(U1-P5.7_UCA2STE_TA4.1_MCLK-Pad68)") (class "Default")
      (node (ref "U1") (pin "68") (pinfunction "P5.7_UCA2STE_TA4.1_MCLK_68") (pintype "bidirectional"))
    )
    (net (code "85") (name "unconnected-(U1-P6.2_UCA3CLK-Pad10)") (class "Default")
      (node (ref "U1") (pin "10") (pinfunction "P6.2_UCA3CLK_10") (pintype "bidirectional"))
    )
    (net (code "86") (name "unconnected-(U1-P6.3_UCA3STE-Pad11)") (class "Default")
      (node (ref "U1") (pin "11") (pinfunction "P6.3_UCA3STE_11") (pintype "bidirectional"))
    )
    (net (code "87") (name "unconnected-(U1-P6.6_UCB3CLK-Pad71)") (class "Default")
      (node (ref "U1") (pin "71") (pinfunction "P6.6_UCB3CLK_71") (pintype "bidirectional"))
    )
    (net (code "88") (name "unconnected-(U1-P6.7_UCB3STE-Pad72)") (class "Default")
      (node (ref "U1") (pin "72") (pinfunction "P6.7_UCB3STE_72") (pintype "bidirectional"))
    )
    (net (code "89") (name "unconnected-(U1-P7.3_UCB2STE_TA4.1-Pad26)") (class "Default")
      (node (ref "U1") (pin "26") (pinfunction "P7.3_UCB2STE_TA4.1_26") (pintype "bidirectional"))
    )
    (net (code "90") (name "unconnected-(U1-P7.4__TA4.0_A16-Pad27)") (class "Default")
      (node (ref "U1") (pin "27") (pinfunction "P7.4__TA4.0_A16_27") (pintype "bidirectional"))
    )
    (net (code "91") (name "unconnected-(U1-P7.5_A17-Pad28)") (class "Default")
      (node (ref "U1") (pin "28") (pinfunction "P7.5_A17_28") (pintype "bidirectional"))
    )
    (net (code "92") (name "unconnected-(U1-P7.6_A18-Pad29)") (class "Default")
      (node (ref "U1") (pin "29") (pinfunction "P7.6_A18_29") (pintype "bidirectional"))
    )
    (net (code "93") (name "unconnected-(U1-P7.7_A19-Pad30)") (class "Default")
      (node (ref "U1") (pin "30") (pinfunction "P7.7_A19_30") (pintype "bidirectional"))
    )
    (net (code "94") (name "unconnected-(U1-P8.1-Pad44)") (class "Default")
      (node (ref "U1") (pin "44") (pinfunction "P8.1_44") (pintype "bidirectional"))
    )
    (net (code "95") (name "unconnected-(U1-P8.2-Pad45)") (class "Default")
      (node (ref "U1") (pin "45") (pinfunction "P8.2_45") (pintype "bidirectional"))
    )
    (net (code "96") (name "unconnected-(U1-P8.3-Pad46)") (class "Default")
      (node (ref "U1") (pin "46") (pinfunction "P8.3_46") (pintype "bidirectional"))
    )
    (net (code "97") (name "unconnected-(U1-PJ.0_TDO_TB0OUTH_SMCLK_SRSCG1_C6-Pad21)") (class "Default")
      (node (ref "U1") (pin "21") (pinfunction "PJ.0_TDO_TB0OUTH_SMCLK_SRSCG1_C6_21") (pintype "bidirectional"))
    )
    (net (code "98") (name "unconnected-(U1-PJ.1_TDI_TCLK_MCLK_SRSCG0_C7-Pad22)") (class "Default")
      (node (ref "U1") (pin "22") (pinfunction "PJ.1_TDI_TCLK_MCLK_SRSCG0_C7_22") (pintype "bidirectional"))
    )
    (net (code "99") (name "unconnected-(U1-PJ.2_TMS_ACLK_SROSCOFF_C8-Pad23)") (class "Default")
      (node (ref "U1") (pin "23") (pinfunction "PJ.2_TMS_ACLK_SROSCOFF_C8_23") (pintype "bidirectional"))
    )
    (net (code "100") (name "unconnected-(U1-PJ.3_TCK_SRCPUOFF_C9-Pad24)") (class "Default")
      (node (ref "U1") (pin "24") (pinfunction "PJ.3_TCK_SRCPUOFF_C9_24") (pintype "bidirectional"))
    )
  )
)
